# ReboostV2_Bridge.net
KiCad netlist of a schematic drawn in Altium Designer
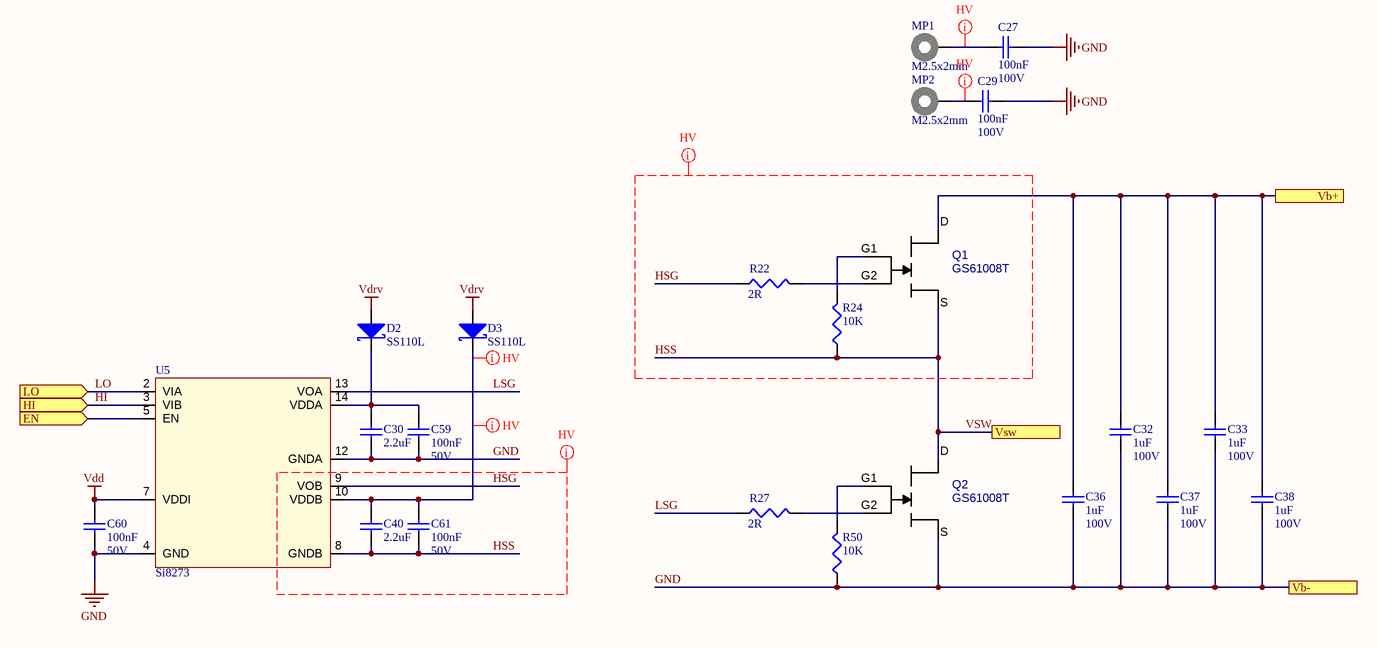
[diagram p0: ReboostV2_Bridge.SchDoc]

(export (version "E")
  (design (tool "Eeschema 10.0.6"))
  (components
    (comp (ref "C27")
      (value "100nF")
      (footprint "C-0805")
      (description "Capacitor, 100nF, 100V, X7R")
      (fields (field (name "VOLTAGE RATING") "100V"))
      (libsource (lib "AR_Capacitors_Ceramic") (part "100nF/0805/CER/100V"))
    )
    (comp (ref "C29")
      (value "100nF")
      (footprint "C-0805")
      (description "Capacitor, 100nF, 100V, X7R")
      (fields (field (name "VOLTAGE RATING") "100V"))
      (libsource (lib "AR_Capacitors_Ceramic") (part "100nF/0805/CER/100V"))
    )
    (comp (ref "C30")
      (value "2.2uF")
      (footprint "C0603")
      (description "Capacitor, 2.2uF, 16V, X5R")
      (libsource (lib "AR_Capacitors_Ceramic") (part "2.2uF/0603/CER/16V"))
    )
    (comp (ref "C32")
      (value "1uF")
      (footprint "C-1206")
      (description "Capacitor, 1uF, 100V, X7R")
      (fields (field (name "VOLTAGE RATING") "100V"))
      (libsource (lib "AR_Capacitors_Ceramic") (part "1uF/1206/CER/100V"))
    )
    (comp (ref "C33")
      (value "1uF")
      (footprint "C-1206")
      (description "Capacitor, 1uF, 100V, X7R")
      (fields (field (name "VOLTAGE RATING") "100V"))
      (libsource (lib "AR_Capacitors_Ceramic") (part "1uF/1206/CER/100V"))
    )
    (comp (ref "C36")
      (value "1uF")
      (footprint "C-1206")
      (description "Capacitor, 1uF, 100V, X7R")
      (fields (field (name "VOLTAGE RATING") "100V"))
      (libsource (lib "AR_Capacitors_Ceramic") (part "1uF/1206/CER/100V"))
    )
    (comp (ref "C37")
      (value "1uF")
      (footprint "C-1206")
      (description "Capacitor, 1uF, 100V, X7R")
      (fields (field (name "VOLTAGE RATING") "100V"))
      (libsource (lib "AR_Capacitors_Ceramic") (part "1uF/1206/CER/100V"))
    )
    (comp (ref "C38")
      (value "1uF")
      (footprint "C-1206")
      (description "Capacitor, 1uF, 100V, X7R")
      (fields (field (name "VOLTAGE RATING") "100V"))
      (libsource (lib "AR_Capacitors_Ceramic") (part "1uF/1206/CER/100V"))
    )
    (comp (ref "C40")
      (value "2.2uF")
      (footprint "C0603")
      (description "Capacitor, 2.2uF, 16V, X5R")
      (libsource (lib "AR_Capacitors_Ceramic") (part "2.2uF/0603/CER/16V"))
    )
    (comp (ref "C59")
      (value "100nF")
      (footprint "C0603")
      (description "Capacitor, 100nF, 50V, X7R")
      (fields (field (name "VOLTAGE RATING") "50V"))
      (libsource (lib "AR_Capacitors_Ceramic") (part "100nF/0603/CER/50V"))
    )
    (comp (ref "C60")
      (value "100nF")
      (footprint "C0603")
      (description "Capacitor, 100nF, 50V, X7R")
      (fields (field (name "VOLTAGE RATING") "50V"))
      (libsource (lib "AR_Capacitors_Ceramic") (part "100nF/0603/CER/50V"))
    )
    (comp (ref "C61")
      (value "100nF")
      (footprint "C0603")
      (description "Capacitor, 100nF, 50V, X7R")
      (fields (field (name "VOLTAGE RATING") "50V"))
      (libsource (lib "AR_Capacitors_Ceramic") (part "100nF/0603/CER/50V"))
    )
    (comp (ref "D2")
      (value "SS110L")
      (footprint "SUB-SMA")
      (description "Diode Schottky, Vrrm: 100V, If: 1A, Vf: 0.9V")
      (libsource (lib "AR_Diodes") (part "SS110L"))
    )
    (comp (ref "D3")
      (value "SS110L")
      (footprint "SUB-SMA")
      (description "Diode Schottky, Vrrm: 100V, If: 1A, Vf: 0.9V")
      (libsource (lib "AR_Diodes") (part "SS110L"))
    )
    (comp (ref "MP1")
      (value "M2.5x2mm")
      (footprint "9774020151")
      (description "WA-SMSI SMT Steel Spacer, M2.5 Thread Internal, OD 5.1mm, M2.5x2mm")
      (fields
        (field (name "MANUFACTURER PART NUMBER") "9774020151")
        (field (name "MANUFACTURER") "Wurth Elektronik")
      )
      (libsource (lib "Altium_SMSI (rev20c)") (part "9774020151"))
    )
    (comp (ref "MP2")
      (value "M2.5x2mm")
      (footprint "9774020151")
      (description "WA-SMSI SMT Steel Spacer, M2.5 Thread Internal, OD 5.1mm, M2.5x2mm")
      (fields
        (field (name "MANUFACTURER PART NUMBER") "9774020151")
        (field (name "MANUFACTURER") "Wurth Elektronik")
      )
      (libsource (lib "Altium_SMSI (rev20c)") (part "9774020151"))
    )
    (comp (ref "Q1")
      (value "GS61008T")
      (footprint "GS61008T")
      (description "GAN TRANS E-MODE 100V 90A TOP SIDE COOL")
      (libsource (lib "AR_Transistors") (part "GS61008T"))
    )
    (comp (ref "Q2")
      (value "GS61008T")
      (footprint "GS61008T")
      (description "GAN TRANS E-MODE 100V 90A TOP SIDE COOL")
      (libsource (lib "AR_Transistors") (part "GS61008T"))
    )
    (comp (ref "R22")
      (value "2R")
      (footprint "0603")
      (description "Resistor, 2R, 5%, 0.1W, 75V, 200PPM, 0603")
      (libsource (lib "AR_Resistors_SMD") (part "2/0603/0100W/75V"))
    )
    (comp (ref "R24")
      (value "10K")
      (footprint "0603")
      (description "Resistor, 10K, 1%, 0.063W, 50V, 100PPM, 0603")
      (libsource (lib "AR_Resistors_SMD") (part "10K/0603/0063W/50V"))
    )
    (comp (ref "R27")
      (value "2R")
      (footprint "0603")
      (description "Resistor, 2R, 5%, 0.1W, 75V, 200PPM, 0603")
      (libsource (lib "AR_Resistors_SMD") (part "2/0603/0100W/75V"))
    )
    (comp (ref "R50")
      (value "10K")
      (footprint "0603")
      (description "Resistor, 10K, 1%, 0.063W, 50V, 100PPM, 0603")
      (libsource (lib "AR_Resistors_SMD") (part "10K/0603/0063W/50V"))
    )
    (comp (ref "U5")
      (value "Si8273")
      (footprint "DFN-14")
      (description "4 Amp ISOdriver with High Transient (dV/dt) Immunity")
      (libsource (lib "AR_ICs") (part "Si8273ABIM1"))
    )
  )
  (nets
    (net (code "1") (name "/EN") (class "Default")
      (node (ref "U5") (pin "5") (pinfunction "EN_5") (pintype "passive"))
    )
    (net (code "2") (name "/HI") (class "Default")
      (node (ref "U5") (pin "3") (pinfunction "VIB_3") (pintype "passive"))
    )
    (net (code "3") (name "/HSG") (class "Default")
      (node (ref "R22") (pin "1") (pinfunction "1_1") (pintype "passive"))
      (node (ref "U5") (pin "9") (pinfunction "VOB_9") (pintype "passive"))
    )
    (net (code "4") (name "/HSS") (class "Default")
      (node (ref "C40") (pin "1") (pinfunction "1_1") (pintype "passive"))
      (node (ref "C61") (pin "1") (pinfunction "1_1") (pintype "passive"))
      (node (ref "Q1") (pin "S") (pinfunction "S_S") (pintype "passive"))
      (node (ref "Q2") (pin "D") (pinfunction "D_D") (pintype "passive"))
      (node (ref "R24") (pin "1") (pinfunction "1_1") (pintype "passive"))
      (node (ref "U5") (pin "8") (pinfunction "GNDB_8") (pintype "passive"))
    )
    (net (code "5") (name "/LO") (class "Default")
      (node (ref "U5") (pin "2") (pinfunction "VIA_2") (pintype "passive"))
    )
    (net (code "6") (name "/LSG") (class "Default")
      (node (ref "R27") (pin "1") (pinfunction "1_1") (pintype "passive"))
      (node (ref "U5") (pin "13") (pinfunction "VOA_13") (pintype "passive"))
    )
    (net (code "7") (name "/Vb+") (class "Default")
      (node (ref "C32") (pin "2") (pinfunction "2_2") (pintype "passive"))
      (node (ref "C33") (pin "2") (pinfunction "2_2") (pintype "passive"))
      (node (ref "C36") (pin "2") (pinfunction "2_2") (pintype "passive"))
      (node (ref "C37") (pin "2") (pinfunction "2_2") (pintype "passive"))
      (node (ref "C38") (pin "2") (pinfunction "2_2") (pintype "passive"))
      (node (ref "Q1") (pin "D") (pinfunction "D_D") (pintype "passive"))
    )
    (net (code "8") (name "GND") (class "Default")
      (node (ref "C27") (pin "1") (pinfunction "1_1") (pintype "passive"))
      (node (ref "C29") (pin "1") (pinfunction "1_1") (pintype "passive"))
      (node (ref "C30") (pin "1") (pinfunction "1_1") (pintype "passive"))
      (node (ref "C32") (pin "1") (pinfunction "1_1") (pintype "passive"))
      (node (ref "C33") (pin "1") (pinfunction "1_1") (pintype "passive"))
      (node (ref "C36") (pin "1") (pinfunction "1_1") (pintype "passive"))
      (node (ref "C37") (pin "1") (pinfunction "1_1") (pintype "passive"))
      (node (ref "C38") (pin "1") (pinfunction "1_1") (pintype "passive"))
      (node (ref "C59") (pin "1") (pinfunction "1_1") (pintype "passive"))
      (node (ref "C60") (pin "1") (pinfunction "1_1") (pintype "passive"))
      (node (ref "Q2") (pin "S") (pinfunction "S_S") (pintype "passive"))
      (node (ref "R50") (pin "1") (pinfunction "1_1") (pintype "passive"))
      (node (ref "U5") (pin "12") (pinfunction "GNDA_12") (pintype "passive"))
      (node (ref "U5") (pin "4") (pinfunction "GND_4") (pintype "passive"))
    )
    (net (code "9") (name "Net-(C27-Pad2)") (class "Default")
      (node (ref "C27") (pin "2") (pinfunction "2_2") (pintype "passive"))
      (node (ref "MP1") (pin "1") (pinfunction "1_1") (pintype "passive"))
    )
    (net (code "10") (name "Net-(C29-Pad2)") (class "Default")
      (node (ref "C29") (pin "2") (pinfunction "2_2") (pintype "passive"))
      (node (ref "MP2") (pin "1") (pinfunction "1_1") (pintype "passive"))
    )
    (net (code "11") (name "Net-(D2-K)") (class "Default")
      (node (ref "C30") (pin "2") (pinfunction "2_2") (pintype "passive"))
      (node (ref "C59") (pin "2") (pinfunction "2_2") (pintype "passive"))
      (node (ref "D2") (pin "2") (pinfunction "K_2") (pintype "passive"))
      (node (ref "U5") (pin "14") (pinfunction "VDDA_14") (pintype "passive"))
    )
    (net (code "12") (name "Net-(D3-K)") (class "Default")
      (node (ref "C40") (pin "2") (pinfunction "2_2") (pintype "passive"))
      (node (ref "C61") (pin "2") (pinfunction "2_2") (pintype "passive"))
      (node (ref "D3") (pin "2") (pinfunction "K_2") (pintype "passive"))
      (node (ref "U5") (pin "10") (pinfunction "VDDB_10") (pintype "passive"))
    )
    (net (code "13") (name "Net-(Q1-PadG1)") (class "Default")
      (node (ref "Q1") (pin "G1") (pinfunction "G1_G1") (pintype "passive"))
      (node (ref "R24") (pin "2") (pinfunction "2_2") (pintype "passive"))
    )
    (net (code "14") (name "Net-(Q1-PadG2)") (class "Default")
      (node (ref "Q1") (pin "G2") (pinfunction "G2_G2") (pintype "passive"))
      (node (ref "R22") (pin "2") (pinfunction "2_2") (pintype "passive"))
    )
    (net (code "15") (name "Net-(Q2-PadG1)") (class "Default")
      (node (ref "Q2") (pin "G1") (pinfunction "G1_G1") (pintype "passive"))
      (node (ref "R50") (pin "2") (pinfunction "2_2") (pintype "passive"))
    )
    (net (code "16") (name "Net-(Q2-PadG2)") (class "Default")
      (node (ref "Q2") (pin "G2") (pinfunction "G2_G2") (pintype "passive"))
      (node (ref "R27") (pin "2") (pinfunction "2_2") (pintype "passive"))
    )
    (net (code "17") (name "Vdd") (class "Default")
      (node (ref "C60") (pin "2") (pinfunction "2_2") (pintype "passive"))
      (node (ref "U5") (pin "7") (pinfunction "VDDI_7") (pintype "passive"))
    )
    (net (code "18") (name "Vdrv") (class "Default")
      (node (ref "D2") (pin "1") (pinfunction "A_1") (pintype "passive"))
      (node (ref "D3") (pin "1") (pinfunction "A_1") (pintype "passive"))
    )
  )
)
